# RTM_CON.net
KiCad netlist of a schematic drawn in Altium Designer
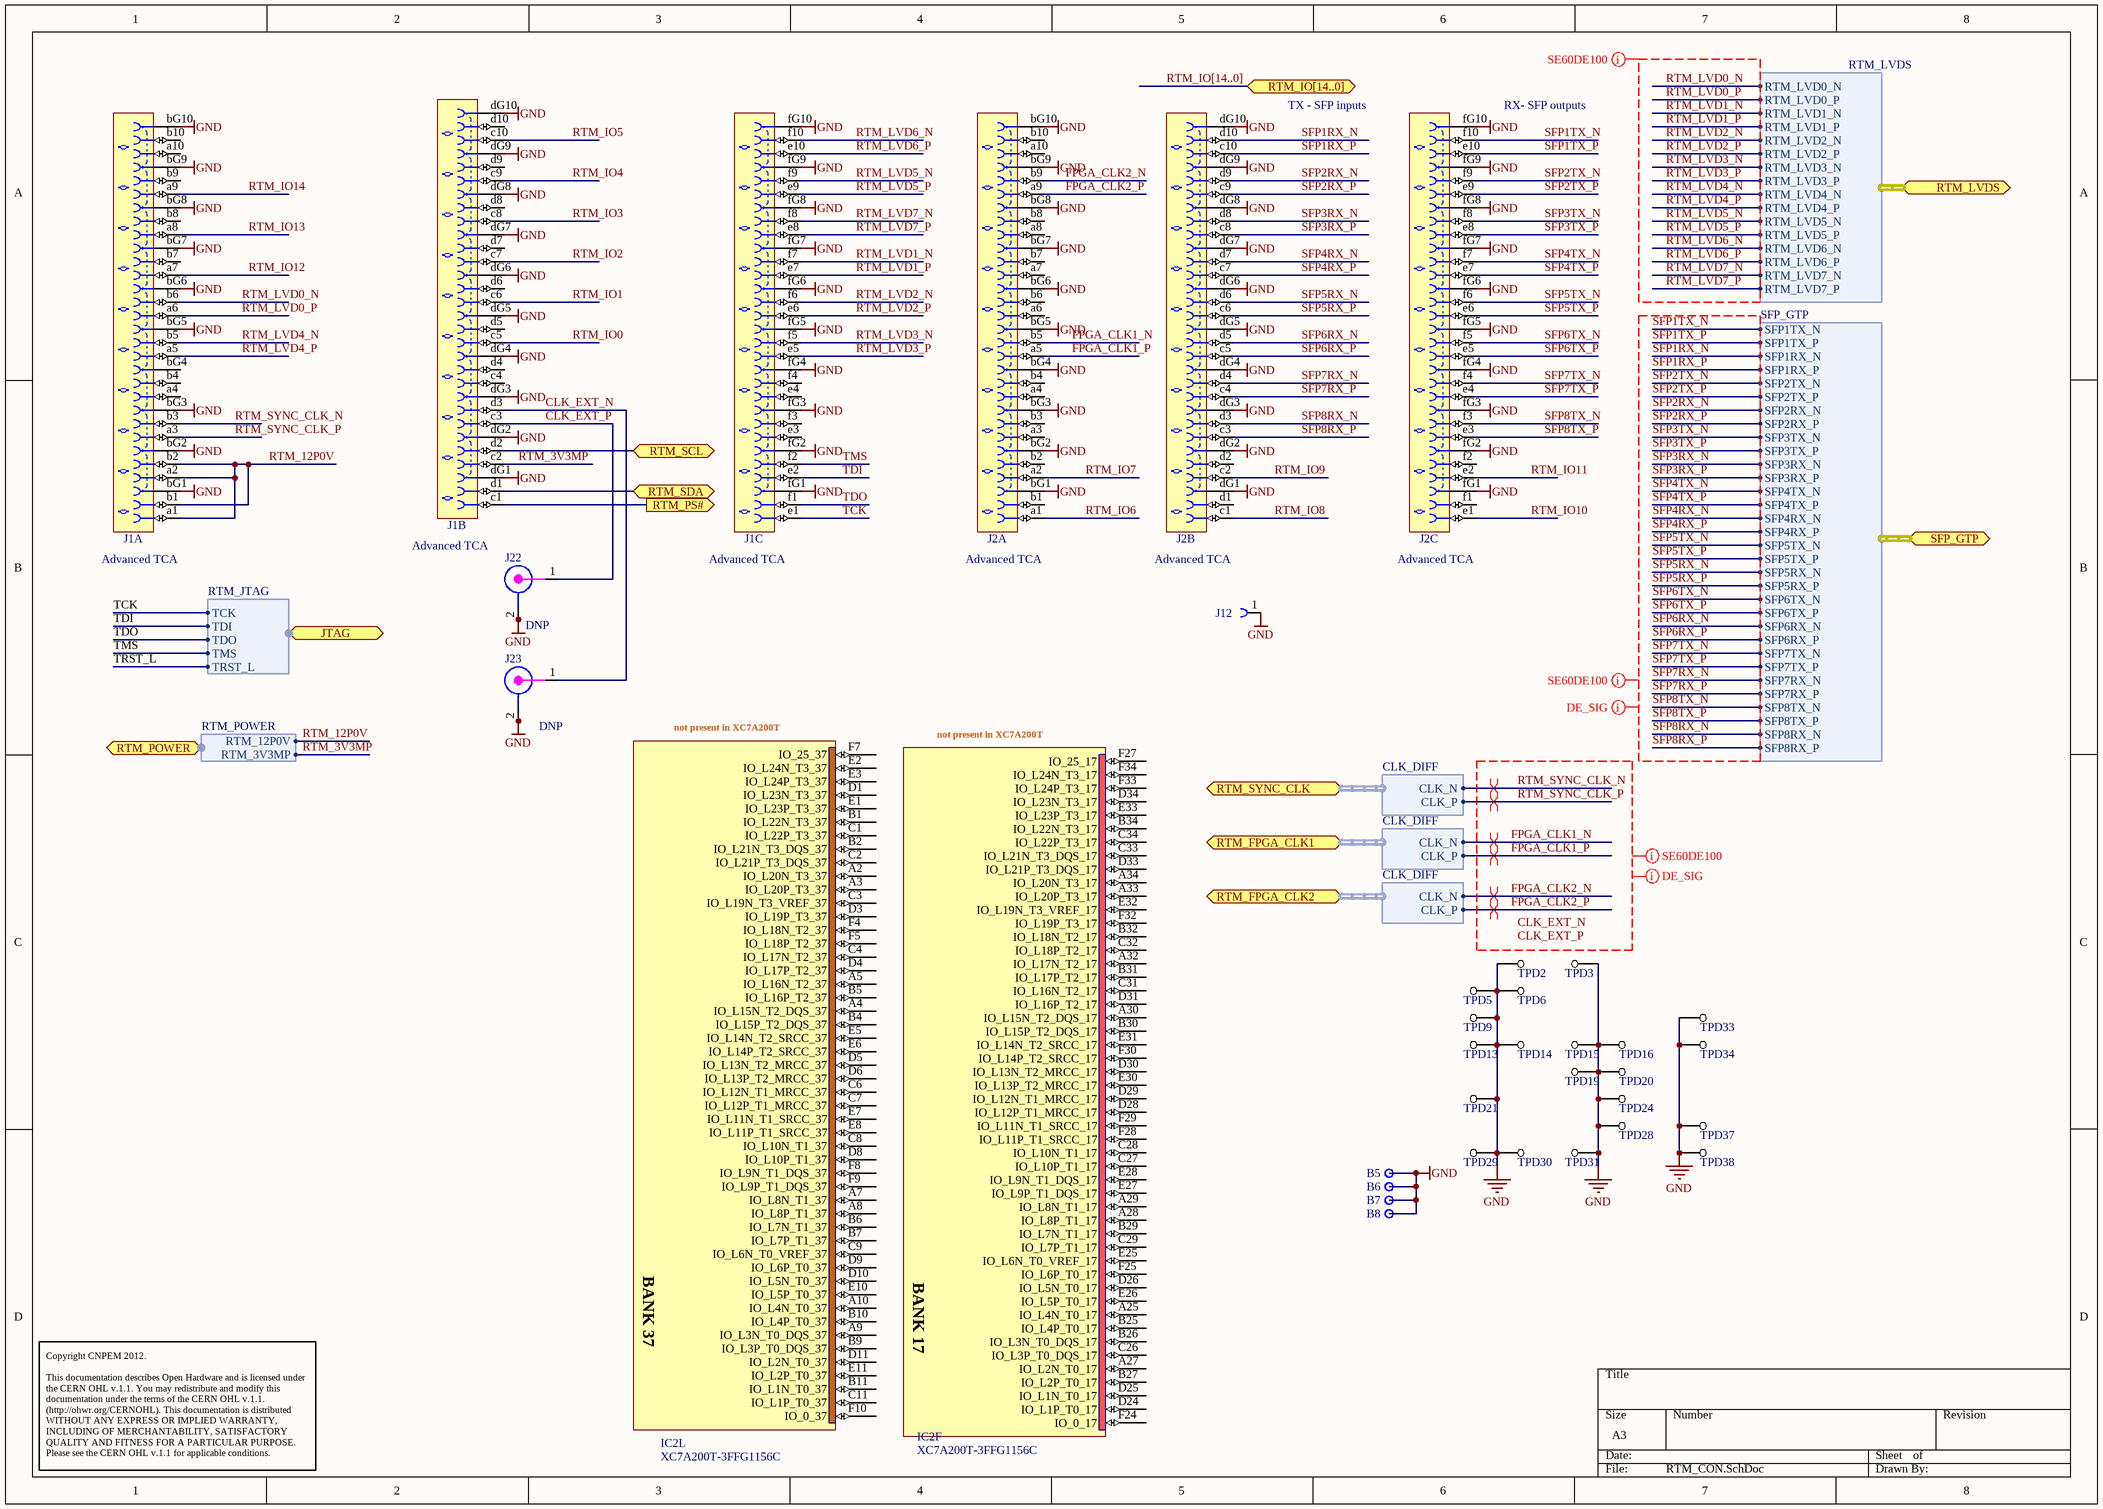
[diagram p0: RTM_CON.SchDoc]

(export (version "E")
  (design (tool "Eeschema 10.0.6"))
  (components
    (comp (ref "B5")
      (value "Test Point")
      (footprint "VERO_20-2136")
      (description "Single Terminal Socket")
      (fields
        (field (name "PART NUMBER") "VERO_20-2136")
        (field (name "MANUFACTURER") "VERO TECHNOLOGIES")
        (field (name "AUTHOR") "CERN DEM JLC")
      )
      (libsource (lib "Connectors") (part "Single Terminal Socket"))
    )
    (comp (ref "B6")
      (value "Test Point")
      (footprint "VERO_20-2136")
      (description "Single Terminal Socket")
      (fields
        (field (name "PART NUMBER") "VERO_20-2136")
        (field (name "MANUFACTURER") "VERO TECHNOLOGIES")
        (field (name "AUTHOR") "CERN DEM JLC")
      )
      (libsource (lib "Connectors") (part "Single Terminal Socket"))
    )
    (comp (ref "B7")
      (value "Test Point")
      (footprint "VERO_20-2136")
      (description "Single Terminal Socket")
      (fields
        (field (name "PART NUMBER") "VERO_20-2136")
        (field (name "MANUFACTURER") "VERO TECHNOLOGIES")
        (field (name "AUTHOR") "CERN DEM JLC")
      )
      (libsource (lib "Connectors") (part "Single Terminal Socket"))
    )
    (comp (ref "B8")
      (value "Test Point")
      (footprint "VERO_20-2136")
      (description "Single Terminal Socket")
      (fields
        (field (name "PART NUMBER") "VERO_20-2136")
        (field (name "MANUFACTURER") "VERO TECHNOLOGIES")
        (field (name "AUTHOR") "CERN DEM JLC")
      )
      (libsource (lib "Connectors") (part "Single Terminal Socket"))
    )
    (comp (ref "IC2")
      (value "XC7A200T-3FFG1156C")
      (footprint "BGA1156C100P34X34_3500X3500X335")
      (description "Artix-6 FPGA, 16 GTPs, 600 User I/Os, 1156-Pin BGA, Speed Grade 2, Commercial Grade, Pb-Free")
      (fields (field (name "MANUFACTURER") "XILINX") (field (name "AUTHOR") "CERN DEM JLC"))
      (libsource (lib "AMC_FMC_Carrier") (part "XC7A200T-3FFG1156C"))
    )
    (comp (ref "J1")
      (value "Advanced TCA")
      (footprint "TYCO_6469081-1")
      (description "Connector 60 ATCA Female 30 Pairs (60 Signals) + 3x10 Ground")
      (fields
        (field (name "PART NUMBER") "TYCO_6469081-1")
        (field (name "MANUFACTURER") "TYCO ELECTRONICS")
        (field (name "AUTHOR") "CERN DEM JLC")
      )
      (libsource (lib "Connectors") (part "Connector ATCA 60+30 Female"))
    )
    (comp (ref "J2")
      (value "Advanced TCA")
      (footprint "TYCO_6469081-1")
      (description "Connector 60 ATCA Female 30 Pairs (60 Signals) + 3x10 Ground")
      (fields
        (field (name "PART NUMBER") "TYCO_6469081-1")
        (field (name "MANUFACTURER") "TYCO ELECTRONICS")
        (field (name "AUTHOR") "CERN DEM JLC")
      )
      (libsource (lib "Connectors") (part "Connector ATCA 60+30 Female"))
    )
    (comp (ref "J12")
      (value "~")
      (footprint "TYCO_5120913-1")
      (description "Single Pin Female")
      (fields (field (name "PART NUMBER") "TYCO_5120913-1"))
      (libsource (lib "Connectors") (part "Single Pin Female"))
    )
    (comp (ref "J22")
      (value "DNP")
      (footprint "CON_UFL_HIROSE_RECEPTACLE")
      (description "UFL")
      (libsource (lib "LIBRARY_SCH") (part "CON_UFL_SMD"))
    )
    (comp (ref "J23")
      (value "DNP")
      (footprint "CON_UFL_HIROSE_RECEPTACLE")
      (description "UFL")
      (libsource (lib "LIBRARY_SCH") (part "CON_UFL_SMD"))
    )
    (comp (ref "TPD2")
      (value "Test Point")
      (footprint "TP_DIFF_0805")
      (description "1625854-2")
      (fields (field (name "PART NUMBER") "TP_DIFF"))
      (libsource (lib "Markers") (part "TP_SMD_DIFF"))
    )
    (comp (ref "TPD3")
      (value "Test Point")
      (footprint "TP_DIFF_0805")
      (description "1625854-2")
      (fields (field (name "PART NUMBER") "TP_DIFF"))
      (libsource (lib "Markers") (part "TP_SMD_DIFF"))
    )
    (comp (ref "TPD5")
      (value "Test Point")
      (footprint "TP_DIFF_0805")
      (description "1625854-2")
      (fields (field (name "PART NUMBER") "TP_DIFF"))
      (libsource (lib "Markers") (part "TP_SMD_DIFF"))
    )
    (comp (ref "TPD6")
      (value "Test Point")
      (footprint "TP_DIFF_0805")
      (description "1625854-2")
      (fields (field (name "PART NUMBER") "TP_DIFF"))
      (libsource (lib "Markers") (part "TP_SMD_DIFF"))
    )
    (comp (ref "TPD9")
      (value "Test Point")
      (footprint "TP_DIFF_0805")
      (description "1625854-2")
      (fields (field (name "PART NUMBER") "TP_DIFF"))
      (libsource (lib "Markers") (part "TP_SMD_DIFF"))
    )
    (comp (ref "TPD13")
      (value "Test Point")
      (footprint "TP_DIFF_0805")
      (description "1625854-2")
      (fields (field (name "PART NUMBER") "TP_DIFF"))
      (libsource (lib "Markers") (part "TP_SMD_DIFF"))
    )
    (comp (ref "TPD14")
      (value "Test Point")
      (footprint "TP_DIFF_0805")
      (description "1625854-2")
      (fields (field (name "PART NUMBER") "TP_DIFF"))
      (libsource (lib "Markers") (part "TP_SMD_DIFF"))
    )
    (comp (ref "TPD15")
      (value "Test Point")
      (footprint "TP_DIFF_0805")
      (description "1625854-2")
      (fields (field (name "PART NUMBER") "TP_DIFF"))
      (libsource (lib "Markers") (part "TP_SMD_DIFF"))
    )
    (comp (ref "TPD16")
      (value "Test Point")
      (footprint "TP_DIFF_0805")
      (description "1625854-2")
      (fields (field (name "PART NUMBER") "TP_DIFF"))
      (libsource (lib "Markers") (part "TP_SMD_DIFF"))
    )
    (comp (ref "TPD19")
      (value "Test Point")
      (footprint "TP_DIFF_0805")
      (description "1625854-2")
      (fields (field (name "PART NUMBER") "TP_DIFF"))
      (libsource (lib "Markers") (part "TP_SMD_DIFF"))
    )
    (comp (ref "TPD20")
      (value "Test Point")
      (footprint "TP_DIFF_0805")
      (description "1625854-2")
      (fields (field (name "PART NUMBER") "TP_DIFF"))
      (libsource (lib "Markers") (part "TP_SMD_DIFF"))
    )
    (comp (ref "TPD21")
      (value "Test Point")
      (footprint "TP_DIFF_0805")
      (description "1625854-2")
      (fields (field (name "PART NUMBER") "TP_DIFF"))
      (libsource (lib "Markers") (part "TP_SMD_DIFF"))
    )
    (comp (ref "TPD24")
      (value "Test Point")
      (footprint "TP_DIFF_0805")
      (description "1625854-2")
      (fields (field (name "PART NUMBER") "TP_DIFF"))
      (libsource (lib "Markers") (part "TP_SMD_DIFF"))
    )
    (comp (ref "TPD28")
      (value "Test Point")
      (footprint "TP_DIFF_0805")
      (description "1625854-2")
      (fields (field (name "PART NUMBER") "TP_DIFF"))
      (libsource (lib "Markers") (part "TP_SMD_DIFF"))
    )
    (comp (ref "TPD29")
      (value "Test Point")
      (footprint "TP_DIFF_0805")
      (description "1625854-2")
      (fields (field (name "PART NUMBER") "TP_DIFF"))
      (libsource (lib "Markers") (part "TP_SMD_DIFF"))
    )
    (comp (ref "TPD30")
      (value "Test Point")
      (footprint "TP_DIFF_0805")
      (description "1625854-2")
      (fields (field (name "PART NUMBER") "TP_DIFF"))
      (libsource (lib "Markers") (part "TP_SMD_DIFF"))
    )
    (comp (ref "TPD31")
      (value "Test Point")
      (footprint "TP_DIFF_0805")
      (description "1625854-2")
      (fields (field (name "PART NUMBER") "TP_DIFF"))
      (libsource (lib "Markers") (part "TP_SMD_DIFF"))
    )
    (comp (ref "TPD33")
      (value "Test Point")
      (footprint "TP_DIFF_0805")
      (description "1625854-2")
      (fields (field (name "PART NUMBER") "TP_DIFF"))
      (libsource (lib "Markers") (part "TP_SMD_DIFF"))
    )
    (comp (ref "TPD34")
      (value "Test Point")
      (footprint "TP_DIFF_0805")
      (description "1625854-2")
      (fields (field (name "PART NUMBER") "TP_DIFF"))
      (libsource (lib "Markers") (part "TP_SMD_DIFF"))
    )
    (comp (ref "TPD37")
      (value "Test Point")
      (footprint "TP_DIFF_0805")
      (description "1625854-2")
      (fields (field (name "PART NUMBER") "TP_DIFF"))
      (libsource (lib "Markers") (part "TP_SMD_DIFF"))
    )
    (comp (ref "TPD38")
      (value "Test Point")
      (footprint "TP_DIFF_0805")
      (description "1625854-2")
      (fields (field (name "PART NUMBER") "TP_DIFF"))
      (libsource (lib "Markers") (part "TP_SMD_DIFF"))
    )
  )
  (nets
    (net (code "6") (name "/CLK_EXT_N") (class "Default")
      (node (ref "J1") (pin "d3") (pinfunction "d3_d3") (pintype "bidirectional"))
      (node (ref "J23") (pin "1") (pintype "passive"))
    )
    (net (code "7") (name "/CLK_EXT_P") (class "Default")
      (node (ref "J1") (pin "c3") (pinfunction "c3_c3") (pintype "bidirectional"))
      (node (ref "J22") (pin "1") (pintype "passive"))
    )
    (net (code "8") (name "/FPGA_CLK1_N") (class "Default")
      (node (ref "J2") (pin "b5") (pinfunction "b5_b5") (pintype "bidirectional"))
    )
    (net (code "9") (name "/FPGA_CLK1_P") (class "Default")
      (node (ref "J2") (pin "a5") (pinfunction "a5_a5") (pintype "bidirectional"))
    )
    (net (code "10") (name "/FPGA_CLK2_N") (class "Default")
      (node (ref "J2") (pin "b9") (pinfunction "b9_b9") (pintype "bidirectional"))
    )
    (net (code "11") (name "/FPGA_CLK2_P") (class "Default")
      (node (ref "J2") (pin "a9") (pinfunction "a9_a9") (pintype "bidirectional"))
    )
    (net (code "12") (name "/RTM_3V3MP") (class "Default")
      (node (ref "J1") (pin "c2") (pinfunction "c2_c2") (pintype "bidirectional"))
    )
    (net (code "13") (name "/RTM_12P0V") (class "Default")
      (node (ref "J1") (pin "a1") (pinfunction "a1_a1") (pintype "bidirectional"))
      (node (ref "J1") (pin "a2") (pinfunction "a2_a2") (pintype "bidirectional"))
      (node (ref "J1") (pin "b1") (pinfunction "b1_b1") (pintype "bidirectional"))
      (node (ref "J1") (pin "b2") (pinfunction "b2_b2") (pintype "bidirectional"))
    )
    (net (code "14") (name "/RTM_IO0") (class "Default")
      (node (ref "J1") (pin "c5") (pinfunction "c5_c5") (pintype "bidirectional"))
    )
    (net (code "15") (name "/RTM_IO1") (class "Default")
      (node (ref "J1") (pin "c6") (pinfunction "c6_c6") (pintype "bidirectional"))
    )
    (net (code "16") (name "/RTM_IO2") (class "Default")
      (node (ref "J1") (pin "c7") (pinfunction "c7_c7") (pintype "bidirectional"))
    )
    (net (code "17") (name "/RTM_IO3") (class "Default")
      (node (ref "J1") (pin "c8") (pinfunction "c8_c8") (pintype "bidirectional"))
    )
    (net (code "18") (name "/RTM_IO4") (class "Default")
      (node (ref "J1") (pin "c9") (pinfunction "c9_c9") (pintype "bidirectional"))
    )
    (net (code "19") (name "/RTM_IO5") (class "Default")
      (node (ref "J1") (pin "c10") (pinfunction "c10_c10") (pintype "bidirectional"))
    )
    (net (code "20") (name "/RTM_IO6") (class "Default")
      (node (ref "J2") (pin "a1") (pinfunction "a1_a1") (pintype "bidirectional"))
    )
    (net (code "21") (name "/RTM_IO7") (class "Default")
      (node (ref "J2") (pin "a2") (pinfunction "a2_a2") (pintype "bidirectional"))
    )
    (net (code "22") (name "/RTM_IO8") (class "Default")
      (node (ref "J2") (pin "c1") (pinfunction "c1_c1") (pintype "bidirectional"))
    )
    (net (code "23") (name "/RTM_IO9") (class "Default")
      (node (ref "J2") (pin "c2") (pinfunction "c2_c2") (pintype "bidirectional"))
    )
    (net (code "24") (name "/RTM_IO10") (class "Default")
      (node (ref "J2") (pin "e1") (pinfunction "e1_e1") (pintype "bidirectional"))
    )
    (net (code "25") (name "/RTM_IO11") (class "Default")
      (node (ref "J2") (pin "e2") (pinfunction "e2_e2") (pintype "bidirectional"))
    )
    (net (code "26") (name "/RTM_IO12") (class "Default")
      (node (ref "J1") (pin "a7") (pinfunction "a7_a7") (pintype "bidirectional"))
    )
    (net (code "27") (name "/RTM_IO13") (class "Default")
      (node (ref "J1") (pin "a8") (pinfunction "a8_a8") (pintype "bidirectional"))
    )
    (net (code "28") (name "/RTM_IO14") (class "Default")
      (node (ref "J1") (pin "a9") (pinfunction "a9_a9") (pintype "bidirectional"))
    )
    (net (code "30") (name "/RTM_LVD0_N") (class "Default")
      (node (ref "J1") (pin "b6") (pinfunction "b6_b6") (pintype "bidirectional"))
    )
    (net (code "31") (name "/RTM_LVD0_P") (class "Default")
      (node (ref "J1") (pin "a6") (pinfunction "a6_a6") (pintype "bidirectional"))
    )
    (net (code "32") (name "/RTM_LVD1_N") (class "Default")
      (node (ref "J1") (pin "f7") (pinfunction "f7_f7") (pintype "bidirectional"))
    )
    (net (code "33") (name "/RTM_LVD1_P") (class "Default")
      (node (ref "J1") (pin "e7") (pinfunction "e7_e7") (pintype "bidirectional"))
    )
    (net (code "34") (name "/RTM_LVD2_N") (class "Default")
      (node (ref "J1") (pin "f6") (pinfunction "f6_f6") (pintype "bidirectional"))
    )
    (net (code "35") (name "/RTM_LVD2_P") (class "Default")
      (node (ref "J1") (pin "e6") (pinfunction "e6_e6") (pintype "bidirectional"))
    )
    (net (code "36") (name "/RTM_LVD3_N") (class "Default")
      (node (ref "J1") (pin "f5") (pinfunction "f5_f5") (pintype "bidirectional"))
    )
    (net (code "37") (name "/RTM_LVD3_P") (class "Default")
      (node (ref "J1") (pin "e5") (pinfunction "e5_e5") (pintype "bidirectional"))
    )
    (net (code "38") (name "/RTM_LVD4_N") (class "Default")
      (node (ref "J1") (pin "b5") (pinfunction "b5_b5") (pintype "bidirectional"))
    )
    (net (code "39") (name "/RTM_LVD4_P") (class "Default")
      (node (ref "J1") (pin "a5") (pinfunction "a5_a5") (pintype "bidirectional"))
    )
    (net (code "40") (name "/RTM_LVD5_N") (class "Default")
      (node (ref "J1") (pin "f9") (pinfunction "f9_f9") (pintype "bidirectional"))
    )
    (net (code "41") (name "/RTM_LVD5_P") (class "Default")
      (node (ref "J1") (pin "e9") (pinfunction "e9_e9") (pintype "bidirectional"))
    )
    (net (code "42") (name "/RTM_LVD6_N") (class "Default")
      (node (ref "J1") (pin "f10") (pinfunction "f10_f10") (pintype "bidirectional"))
    )
    (net (code "43") (name "/RTM_LVD6_P") (class "Default")
      (node (ref "J1") (pin "e10") (pinfunction "e10_e10") (pintype "bidirectional"))
    )
    (net (code "44") (name "/RTM_LVD7_N") (class "Default")
      (node (ref "J1") (pin "f8") (pinfunction "f8_f8") (pintype "bidirectional"))
    )
    (net (code "45") (name "/RTM_LVD7_P") (class "Default")
      (node (ref "J1") (pin "e8") (pinfunction "e8_e8") (pintype "bidirectional"))
    )
    (net (code "46") (name "/RTM_PS#") (class "Default")
      (node (ref "J1") (pin "c1") (pinfunction "c1_c1") (pintype "bidirectional"))
    )
    (net (code "47") (name "/RTM_SCL") (class "Default")
      (node (ref "J1") (pin "d2") (pinfunction "d2_d2") (pintype "bidirectional"))
    )
    (net (code "48") (name "/RTM_SDA") (class "Default")
      (node (ref "J1") (pin "d1") (pinfunction "d1_d1") (pintype "bidirectional"))
    )
    (net (code "49") (name "/RTM_SYNC_CLK_N") (class "Default")
      (node (ref "J1") (pin "b3") (pinfunction "b3_b3") (pintype "bidirectional"))
    )
    (net (code "50") (name "/RTM_SYNC_CLK_P") (class "Default")
      (node (ref "J1") (pin "a3") (pinfunction "a3_a3") (pintype "bidirectional"))
    )
    (net (code "51") (name "/SFP1RX_N") (class "Default")
      (node (ref "J2") (pin "d10") (pinfunction "d10_d10") (pintype "bidirectional"))
    )
    (net (code "52") (name "/SFP1RX_P") (class "Default")
      (node (ref "J2") (pin "c10") (pinfunction "c10_c10") (pintype "bidirectional"))
    )
    (net (code "53") (name "/SFP1TX_N") (class "Default")
      (node (ref "J2") (pin "f10") (pinfunction "f10_f10") (pintype "bidirectional"))
    )
    (net (code "54") (name "/SFP1TX_P") (class "Default")
      (node (ref "J2") (pin "e10") (pinfunction "e10_e10") (pintype "bidirectional"))
    )
    (net (code "55") (name "/SFP2RX_N") (class "Default")
      (node (ref "J2") (pin "d9") (pinfunction "d9_d9") (pintype "bidirectional"))
    )
    (net (code "56") (name "/SFP2RX_P") (class "Default")
      (node (ref "J2") (pin "c9") (pinfunction "c9_c9") (pintype "bidirectional"))
    )
    (net (code "57") (name "/SFP2TX_N") (class "Default")
      (node (ref "J2") (pin "f9") (pinfunction "f9_f9") (pintype "bidirectional"))
    )
    (net (code "58") (name "/SFP2TX_P") (class "Default")
      (node (ref "J2") (pin "e9") (pinfunction "e9_e9") (pintype "bidirectional"))
    )
    (net (code "59") (name "/SFP3RX_N") (class "Default")
      (node (ref "J2") (pin "d8") (pinfunction "d8_d8") (pintype "bidirectional"))
    )
    (net (code "60") (name "/SFP3RX_P") (class "Default")
      (node (ref "J2") (pin "c8") (pinfunction "c8_c8") (pintype "bidirectional"))
    )
    (net (code "61") (name "/SFP3TX_N") (class "Default")
      (node (ref "J2") (pin "f8") (pinfunction "f8_f8") (pintype "bidirectional"))
    )
    (net (code "62") (name "/SFP3TX_P") (class "Default")
      (node (ref "J2") (pin "e8") (pinfunction "e8_e8") (pintype "bidirectional"))
    )
    (net (code "63") (name "/SFP4RX_N") (class "Default")
      (node (ref "J2") (pin "d7") (pinfunction "d7_d7") (pintype "bidirectional"))
    )
    (net (code "64") (name "/SFP4RX_P") (class "Default")
      (node (ref "J2") (pin "c7") (pinfunction "c7_c7") (pintype "bidirectional"))
    )
    (net (code "65") (name "/SFP4TX_N") (class "Default")
      (node (ref "J2") (pin "f7") (pinfunction "f7_f7") (pintype "bidirectional"))
    )
    (net (code "66") (name "/SFP4TX_P") (class "Default")
      (node (ref "J2") (pin "e7") (pinfunction "e7_e7") (pintype "bidirectional"))
    )
    (net (code "67") (name "/SFP5RX_N") (class "Default")
      (node (ref "J2") (pin "d6") (pinfunction "d6_d6") (pintype "bidirectional"))
    )
    (net (code "68") (name "/SFP5RX_P") (class "Default")
      (node (ref "J2") (pin "c6") (pinfunction "c6_c6") (pintype "bidirectional"))
    )
    (net (code "69") (name "/SFP5TX_N") (class "Default")
      (node (ref "J2") (pin "f6") (pinfunction "f6_f6") (pintype "bidirectional"))
    )
    (net (code "70") (name "/SFP5TX_P") (class "Default")
      (node (ref "J2") (pin "e6") (pinfunction "e6_e6") (pintype "bidirectional"))
    )
    (net (code "71") (name "/SFP6RX_N") (class "Default")
      (node (ref "J2") (pin "d5") (pinfunction "d5_d5") (pintype "bidirectional"))
    )
    (net (code "72") (name "/SFP6RX_P") (class "Default")
      (node (ref "J2") (pin "c5") (pinfunction "c5_c5") (pintype "bidirectional"))
    )
    (net (code "73") (name "/SFP6TX_N") (class "Default")
      (node (ref "J2") (pin "f5") (pinfunction "f5_f5") (pintype "bidirectional"))
    )
    (net (code "74") (name "/SFP6TX_P") (class "Default")
      (node (ref "J2") (pin "e5") (pinfunction "e5_e5") (pintype "bidirectional"))
    )
    (net (code "75") (name "/SFP7RX_N") (class "Default")
      (node (ref "J2") (pin "d4") (pinfunction "d4_d4") (pintype "bidirectional"))
    )
    (net (code "76") (name "/SFP7RX_P") (class "Default")
      (node (ref "J2") (pin "c4") (pinfunction "c4_c4") (pintype "bidirectional"))
    )
    (net (code "77") (name "/SFP7TX_N") (class "Default")
      (node (ref "J2") (pin "f4") (pinfunction "f4_f4") (pintype "bidirectional"))
    )
    (net (code "78") (name "/SFP7TX_P") (class "Default")
      (node (ref "J2") (pin "e4") (pinfunction "e4_e4") (pintype "bidirectional"))
    )
    (net (code "79") (name "/SFP8RX_N") (class "Default")
      (node (ref "J2") (pin "d3") (pinfunction "d3_d3") (pintype "bidirectional"))
    )
    (net (code "80") (name "/SFP8RX_P") (class "Default")
      (node (ref "J2") (pin "c3") (pinfunction "c3_c3") (pintype "bidirectional"))
    )
    (net (code "81") (name "/SFP8TX_N") (class "Default")
      (node (ref "J2") (pin "f3") (pinfunction "f3_f3") (pintype "bidirectional"))
    )
    (net (code "82") (name "/SFP8TX_P") (class "Default")
      (node (ref "J2") (pin "e3") (pinfunction "e3_e3") (pintype "bidirectional"))
    )
    (net (code "83") (name "/TCK") (class "Default")
      (node (ref "J1") (pin "e1") (pinfunction "e1_e1") (pintype "bidirectional"))
    )
    (net (code "84") (name "/TDI") (class "Default")
      (node (ref "J1") (pin "e2") (pinfunction "e2_e2") (pintype "bidirectional"))
    )
    (net (code "85") (name "/TDO") (class "Default")
      (node (ref "J1") (pin "f1") (pinfunction "f1_f1") (pintype "bidirectional"))
    )
    (net (code "86") (name "/TMS") (class "Default")
      (node (ref "J1") (pin "f2") (pinfunction "f2_f2") (pintype "bidirectional"))
    )
    (net (code "93") (name "GND") (class "Default")
      (node (ref "B5") (pin "1") (pinfunction "1_1") (pintype "bidirectional"))
      (node (ref "B6") (pin "1") (pinfunction "1_1") (pintype "bidirectional"))
      (node (ref "B7") (pin "1") (pinfunction "1_1") (pintype "bidirectional"))
      (node (ref "B8") (pin "1") (pinfunction "1_1") (pintype "bidirectional"))
      (node (ref "J1") (pin "bG1") (pinfunction "bG1_bG1") (pintype "power_in"))
      (node (ref "J1") (pin "bG10") (pinfunction "bG10_bG10") (pintype "power_in"))
      (node (ref "J1") (pin "bG2") (pinfunction "bG2_bG2") (pintype "power_in"))
      (node (ref "J1") (pin "bG3") (pinfunction "bG3_bG3") (pintype "power_in"))
      (node (ref "J1") (pin "bG5") (pinfunction "bG5_bG5") (pintype "power_in"))
      (node (ref "J1") (pin "bG6") (pinfunction "bG6_bG6") (pintype "power_in"))
      (node (ref "J1") (pin "bG7") (pinfunction "bG7_bG7") (pintype "power_in"))
      (node (ref "J1") (pin "bG8") (pinfunction "bG8_bG8") (pintype "power_in"))
      (node (ref "J1") (pin "bG9") (pinfunction "bG9_bG9") (pintype "power_in"))
      (node (ref "J1") (pin "dG1") (pinfunction "dG1_dG1") (pintype "power_in"))
      (node (ref "J1") (pin "dG10") (pinfunction "dG10_dG10") (pintype "power_in"))
      (node (ref "J1") (pin "dG2") (pinfunction "dG2_dG2") (pintype "power_in"))
      (node (ref "J1") (pin "dG3") (pinfunction "dG3_dG3") (pintype "power_in"))
      (node (ref "J1") (pin "dG4") (pinfunction "dG4_dG4") (pintype "power_in"))
      (node (ref "J1") (pin "dG5") (pinfunction "dG5_dG5") (pintype "power_in"))
      (node (ref "J1") (pin "dG6") (pinfunction "dG6_dG6") (pintype "power_in"))
      (node (ref "J1") (pin "dG7") (pinfunction "dG7_dG7") (pintype "power_in"))
      (node (ref "J1") (pin "dG8") (pinfunction "dG8_dG8") (pintype "power_in"))
      (node (ref "J1") (pin "dG9") (pinfunction "dG9_dG9") (pintype "power_in"))
      (node (ref "J1") (pin "fG1") (pinfunction "fG1_fG1") (pintype "power_in"))
      (node (ref "J1") (pin "fG10") (pinfunction "fG10_fG10") (pintype "power_in"))
      (node (ref "J1") (pin "fG2") (pinfunction "fG2_fG2") (pintype "power_in"))
      (node (ref "J1") (pin "fG3") (pinfunction "fG3_fG3") (pintype "power_in"))
      (node (ref "J1") (pin "fG4") (pinfunction "fG4_fG4") (pintype "power_in"))
      (node (ref "J1") (pin "fG5") (pinfunction "fG5_fG5") (pintype "power_in"))
      (node (ref "J1") (pin "fG6") (pinfunction "fG6_fG6") (pintype "power_in"))
      (node (ref "J1") (pin "fG7") (pinfunction "fG7_fG7") (pintype "power_in"))
      (node (ref "J1") (pin "fG8") (pinfunction "fG8_fG8") (pintype "power_in"))
      (node (ref "J1") (pin "fG9") (pinfunction "fG9_fG9") (pintype "power_in"))
      (node (ref "J12") (pin "1") (pinfunction "1_1") (pintype "bidirectional"))
      (node (ref "J2") (pin "bG1") (pinfunction "bG1_bG1") (pintype "power_in"))
      (node (ref "J2") (pin "bG10") (pinfunction "bG10_bG10") (pintype "power_in"))
      (node (ref "J2") (pin "bG2") (pinfunction "bG2_bG2") (pintype "power_in"))
      (node (ref "J2") (pin "bG3") (pinfunction "bG3_bG3") (pintype "power_in"))
      (node (ref "J2") (pin "bG4") (pinfunction "bG4_bG4") (pintype "power_in"))
      (node (ref "J2") (pin "bG5") (pinfunction "bG5_bG5") (pintype "power_in"))
      (node (ref "J2") (pin "bG6") (pinfunction "bG6_bG6") (pintype "power_in"))
      (node (ref "J2") (pin "bG7") (pinfunction "bG7_bG7") (pintype "power_in"))
      (node (ref "J2") (pin "bG8") (pinfunction "bG8_bG8") (pintype "power_in"))
      (node (ref "J2") (pin "bG9") (pinfunction "bG9_bG9") (pintype "power_in"))
      (node (ref "J2") (pin "dG1") (pinfunction "dG1_dG1") (pintype "power_in"))
      (node (ref "J2") (pin "dG10") (pinfunction "dG10_dG10") (pintype "power_in"))
      (node (ref "J2") (pin "dG2") (pinfunction "dG2_dG2") (pintype "power_in"))
      (node (ref "J2") (pin "dG3") (pinfunction "dG3_dG3") (pintype "power_in"))
      (node (ref "J2") (pin "dG4") (pinfunction "dG4_dG4") (pintype "power_in"))
      (node (ref "J2") (pin "dG5") (pinfunction "dG5_dG5") (pintype "power_in"))
      (node (ref "J2") (pin "dG6") (pinfunction "dG6_dG6") (pintype "power_in"))
      (node (ref "J2") (pin "dG7") (pinfunction "dG7_dG7") (pintype "power_in"))
      (node (ref "J2") (pin "dG8") (pinfunction "dG8_dG8") (pintype "power_in"))
      (node (ref "J2") (pin "dG9") (pinfunction "dG9_dG9") (pintype "power_in"))
      (node (ref "J2") (pin "fG1") (pinfunction "fG1_fG1") (pintype "power_in"))
      (node (ref "J2") (pin "fG10") (pinfunction "fG10_fG10") (pintype "power_in"))
      (node (ref "J2") (pin "fG2") (pinfunction "fG2_fG2") (pintype "power_in"))
      (node (ref "J2") (pin "fG3") (pinfunction "fG3_fG3") (pintype "power_in"))
      (node (ref "J2") (pin "fG4") (pinfunction "fG4_fG4") (pintype "power_in"))
      (node (ref "J2") (pin "fG5") (pinfunction "fG5_fG5") (pintype "power_in"))
      (node (ref "J2") (pin "fG6") (pinfunction "fG6_fG6") (pintype "power_in"))
      (node (ref "J2") (pin "fG7") (pinfunction "fG7_fG7") (pintype "power_in"))
      (node (ref "J2") (pin "fG8") (pinfunction "fG8_fG8") (pintype "power_in"))
      (node (ref "J2") (pin "fG9") (pinfunction "fG9_fG9") (pintype "power_in"))
      (node (ref "J22") (pin "2") (pintype "passive"))
      (node (ref "J22") (pin "2a") (pinfunction "GND_2a") (pintype "passive"))
      (node (ref "J23") (pin "2") (pintype "passive"))
      (node (ref "J23") (pin "2a") (pinfunction "GND_2a") (pintype "passive"))
      (node (ref "TPD13") (pin "1") (pinfunction "TP_1") (pintype "passive"))
      (node (ref "TPD14") (pin "1") (pinfunction "TP_1") (pintype "passive"))
      (node (ref "TPD15") (pin "1") (pinfunction "TP_1") (pintype "passive"))
      (node (ref "TPD16") (pin "1") (pinfunction "TP_1") (pintype "passive"))
      (node (ref "TPD19") (pin "1") (pinfunction "TP_1") (pintype "passive"))
      (node (ref "TPD2") (pin "1") (pinfunction "TP_1") (pintype "passive"))
      (node (ref "TPD20") (pin "1") (pinfunction "TP_1") (pintype "passive"))
      (node (ref "TPD21") (pin "1") (pinfunction "TP_1") (pintype "passive"))
      (node (ref "TPD24") (pin "1") (pinfunction "TP_1") (pintype "passive"))
      (node (ref "TPD28") (pin "1") (pinfunction "TP_1") (pintype "passive"))
      (node (ref "TPD29") (pin "1") (pinfunction "TP_1") (pintype "passive"))
      (node (ref "TPD3") (pin "1") (pinfunction "TP_1") (pintype "passive"))
      (node (ref "TPD30") (pin "1") (pinfunction "TP_1") (pintype "passive"))
      (node (ref "TPD31") (pin "1") (pinfunction "TP_1") (pintype "passive"))
      (node (ref "TPD33") (pin "1") (pinfunction "TP_1") (pintype "passive"))
      (node (ref "TPD34") (pin "1") (pinfunction "TP_1") (pintype "passive"))
      (node (ref "TPD37") (pin "1") (pinfunction "TP_1") (pintype "passive"))
      (node (ref "TPD38") (pin "1") (pinfunction "TP_1") (pintype "passive"))
      (node (ref "TPD5") (pin "1") (pinfunction "TP_1") (pintype "passive"))
      (node (ref "TPD6") (pin "1") (pinfunction "TP_1") (pintype "passive"))
      (node (ref "TPD9") (pin "1") (pinfunction "TP_1") (pintype "passive"))
    )
    (net (code "94") (name "unconnected-(IC2F-IO_0_17-PadF24)") (class "Default")
      (node (ref "IC2") (pin "F24") (pinfunction "IO_0_17_F24") (pintype "bidirectional"))
    )
    (net (code "95") (name "unconnected-(IC2F-IO_25_17-PadF27)") (class "Default")
      (node (ref "IC2") (pin "F27") (pinfunction "IO_25_17_F27") (pintype "bidirectional"))
    )
    (net (code "96") (name "unconnected-(IC2F-IO_L1N_T0_17-PadD25)") (class "Default")
      (node (ref "IC2") (pin "D25") (pinfunction "IO_L1N_T0_17_D25") (pintype "bidirectional"))
    )
    (net (code "97") (name "unconnected-(IC2F-IO_L1P_T0_17-PadD24)") (class "Default")
      (node (ref "IC2") (pin "D24") (pinfunction "IO_L1P_T0_17_D24") (pintype "bidirectional"))
    )
    (net (code "98") (name "unconnected-(IC2F-IO_L2N_T0_17-PadA27)") (class "Default")
      (node (ref "IC2") (pin "A27") (pinfunction "IO_L2N_T0_17_A27") (pintype "bidirectional"))
    )
    (net (code "99") (name "unconnected-(IC2F-IO_L2P_T0_17-PadB27)") (class "Default")
      (node (ref "IC2") (pin "B27") (pinfunction "IO_L2P_T0_17_B27") (pintype "bidirectional"))
    )
    (net (code "100") (name "unconnected-(IC2F-IO_L3N_T0_DQS_17-PadB26)") (class "Default")
      (node (ref "IC2") (pin "B26") (pinfunction "IO_L3N_T0_DQS_17_B26") (pintype "bidirectional"))
    )
    (net (code "101") (name "unconnected-(IC2F-IO_L3P_T0_DQS_17-PadC26)") (class "Default")
      (node (ref "IC2") (pin "C26") (pinfunction "IO_L3P_T0_DQS_17_C26") (pintype "bidirectional"))
    )
    (net (code "102") (name "unconnected-(IC2F-IO_L4N_T0_17-PadA25)") (class "Default")
      (node (ref "IC2") (pin "A25") (pinfunction "IO_L4N_T0_17_A25") (pintype "bidirectional"))
    )
    (net (code "103") (name "unconnected-(IC2F-IO_L4P_T0_17-PadB25)") (class "Default")
      (node (ref "IC2") (pin "B25") (pinfunction "IO_L4P_T0_17_B25") (pintype "bidirectional"))
    )
    (net (code "104") (name "unconnected-(IC2F-IO_L5N_T0_17-PadD26)") (class "Default")
      (node (ref "IC2") (pin "D26") (pinfunction "IO_L5N_T0_17_D26") (pintype "bidirectional"))
    )
    (net (code "105") (name "unconnected-(IC2F-IO_L5P_T0_17-PadE26)") (class "Default")
      (node (ref "IC2") (pin "E26") (pinfunction "IO_L5P_T0_17_E26") (pintype "bidirectional"))
    )
    (net (code "106") (name "unconnected-(IC2F-IO_L6N_T0_VREF_17-PadE25)") (class "Default")
      (node (ref "IC2") (pin "E25") (pinfunction "IO_L6N_T0_VREF_17_E25") (pintype "bidirectional"))
    )
    (net (code "107") (name "unconnected-(IC2F-IO_L6P_T0_17-PadF25)") (class "Default")
      (node (ref "IC2") (pin "F25") (pinfunction "IO_L6P_T0_17_F25") (pintype "bidirectional"))
    )
    (net (code "108") (name "unconnected-(IC2F-IO_L7N_T1_17-PadB29)") (class "Default")
      (node (ref "IC2") (pin "B29") (pinfunction "IO_L7N_T1_17_B29") (pintype "bidirectional"))
    )
    (net (code "109") (name "unconnected-(IC2F-IO_L7P_T1_17-PadC29)") (class "Default")
      (node (ref "IC2") (pin "C29") (pinfunction "IO_L7P_T1_17_C29") (pintype "bidirectional"))
    )
    (net (code "110") (name "unconnected-(IC2F-IO_L8N_T1_17-PadA29)") (class "Default")
      (node (ref "IC2") (pin "A29") (pinfunction "IO_L8N_T1_17_A29") (pintype "bidirectional"))
    )
    (net (code "111") (name "unconnected-(IC2F-IO_L8P_T1_17-PadA28)") (class "Default")
      (node (ref "IC2") (pin "A28") (pinfunction "IO_L8P_T1_17_A28") (pintype "bidirectional"))
    )
    (net (code "112") (name "unconnected-(IC2F-IO_L9N_T1_DQS_17-PadE28)") (class "Default")
      (node (ref "IC2") (pin "E28") (pinfunction "IO_L9N_T1_DQS_17_E28") (pintype "bidirectional"))
    )
    (net (code "113") (name "unconnected-(IC2F-IO_L9P_T1_DQS_17-PadE27)") (class "Default")
      (node (ref "IC2") (pin "E27") (pinfunction "IO_L9P_T1_DQS_17_E27") (pintype "bidirectional"))
    )
    (net (code "114") (name "unconnected-(IC2F-IO_L10N_T1_17-PadC28)") (class "Default")
      (node (ref "IC2") (pin "C28") (pinfunction "IO_L10N_T1_17_C28") (pintype "bidirectional"))
    )
    (net (code "115") (name "unconnected-(IC2F-IO_L10P_T1_17-PadC27)") (class "Default")
      (node (ref "IC2") (pin "C27") (pinfunction "IO_L10P_T1_17_C27") (pintype "bidirectional"))
    )
    (net (code "116") (name "unconnected-(IC2F-IO_L11N_T1_SRCC_17-PadF29)") (class "Default")
      (node (ref "IC2") (pin "F29") (pinfunction "IO_L11N_T1_SRCC_17_F29") (pintype "bidirectional"))
    )
    (net (code "117") (name "unconnected-(IC2F-IO_L11P_T1_SRCC_17-PadF28)") (class "Default")
      (node (ref "IC2") (pin "F28") (pinfunction "IO_L11P_T1_SRCC_17_F28") (pintype "bidirectional"))
    )
    (net (code "118") (name "unconnected-(IC2F-IO_L12N_T1_MRCC_17-PadD29)") (class "Default")
      (node (ref "IC2") (pin "D29") (pinfunction "IO_L12N_T1_MRCC_17_D29") (pintype "bidirectional"))
    )
    (net (code "119") (name "unconnected-(IC2F-IO_L12P_T1_MRCC_17-PadD28)") (class "Default")
      (node (ref "IC2") (pin "D28") (pinfunction "IO_L12P_T1_MRCC_17_D28") (pintype "bidirectional"))
    )
    (net (code "120") (name "unconnected-(IC2F-IO_L13N_T2_MRCC_17-PadD30)") (class "Default")
      (node (ref "IC2") (pin "D30") (pinfunction "IO_L13N_T2_MRCC_17_D30") (pintype "bidirectional"))
    )
    (net (code "121") (name "unconnected-(IC2F-IO_L13P_T2_MRCC_17-PadE30)") (class "Default")
      (node (ref "IC2") (pin "E30") (pinfunction "IO_L13P_T2_MRCC_17_E30") (pintype "bidirectional"))
    )
    (net (code "122") (name "unconnected-(IC2F-IO_L14N_T2_SRCC_17-PadE31)") (class "Default")
      (node (ref "IC2") (pin "E31") (pinfunction "IO_L14N_T2_SRCC_17_E31") (pintype "bidirectional"))
    )
    (net (code "123") (name "unconnected-(IC2F-IO_L14P_T2_SRCC_17-PadF30)") (class "Default")
      (node (ref "IC2") (pin "F30") (pinfunction "IO_L14P_T2_SRCC_17_F30") (pintype "bidirectional"))
    )
    (net (code "124") (name "unconnected-(IC2F-IO_L15N_T2_DQS_17-PadA30)") (class "Default")
      (node (ref "IC2") (pin "A30") (pinfunction "IO_L15N_T2_DQS_17_A30") (pintype "bidirectional"))
    )
    (net (code "125") (name "unconnected-(IC2F-IO_L15P_T2_DQS_17-PadB30)") (class "Default")
      (node (ref "IC2") (pin "B30") (pinfunction "IO_L15P_T2_DQS_17_B30") (pintype "bidirectional"))
    )
    (net (code "126") (name "unconnected-(IC2F-IO_L16N_T2_17-PadC31)") (class "Default")
      (node (ref "IC2") (pin "C31") (pinfunction "IO_L16N_T2_17_C31") (pintype "bidirectional"))
    )
    (net (code "127") (name "unconnected-(IC2F-IO_L16P_T2_17-PadD31)") (class "Default")
      (node (ref "IC2") (pin "D31") (pinfunction "IO_L16P_T2_17_D31") (pintype "bidirectional"))
    )
    (net (code "128") (name "unconnected-(IC2F-IO_L17N_T2_17-PadA32)") (class "Default")
      (node (ref "IC2") (pin "A32") (pinfunction "IO_L17N_T2_17_A32") (pintype "bidirectional"))
    )
    (net (code "129") (name "unconnected-(IC2F-IO_L17P_T2_17-PadB31)") (class "Default")
      (node (ref "IC2") (pin "B31") (pinfunction "IO_L17P_T2_17_B31") (pintype "bidirectional"))
    )
    (net (code "130") (name "unconnected-(IC2F-IO_L18N_T2_17-PadB32)") (class "Default")
      (node (ref "IC2") (pin "B32") (pinfunction "IO_L18N_T2_17_B32") (pintype "bidirectional"))
    )
    (net (code "131") (name "unconnected-(IC2F-IO_L18P_T2_17-PadC32)") (class "Default")
      (node (ref "IC2") (pin "C32") (pinfunction "IO_L18P_T2_17_C32") (pintype "bidirectional"))
    )
    (net (code "132") (name "unconnected-(IC2F-IO_L19N_T3_VREF_17-PadE32)") (class "Default")
      (node (ref "IC2") (pin "E32") (pinfunction "IO_L19N_T3_VREF_17_E32") (pintype "bidirectional"))
    )
    (net (code "133") (name "unconnected-(IC2F-IO_L19P_T3_17-PadF32)") (class "Default")
      (node (ref "IC2") (pin "F32") (pinfunction "IO_L19P_T3_17_F32") (pintype "bidirectional"))
    )
    (net (code "134") (name "unconnected-(IC2F-IO_L20N_T3_17-PadA34)") (class "Default")
      (node (ref "IC2") (pin "A34") (pinfunction "IO_L20N_T3_17_A34") (pintype "bidirectional"))
    )
    (net (code "135") (name "unconnected-(IC2F-IO_L20P_T3_17-PadA33)") (class "Default")
      (node (ref "IC2") (pin "A33") (pinfunction "IO_L20P_T3_17_A33") (pintype "bidirectional"))
    )
    (net (code "136") (name "unconnected-(IC2F-IO_L21N_T3_DQS_17-PadC33)") (class "Default")
      (node (ref "IC2") (pin "C33") (pinfunction "IO_L21N_T3_DQS_17_C33") (pintype "bidirectional"))
    )
    (net (code "137") (name "unconnected-(IC2F-IO_L21P_T3_DQS_17-PadD33)") (class "Default")
      (node (ref "IC2") (pin "D33") (pinfunction "IO_L21P_T3_DQS_17_D33") (pintype "bidirectional"))
    )
    (net (code "138") (name "unconnected-(IC2F-IO_L22N_T3_17-PadB34)") (class "Default")
      (node (ref "IC2") (pin "B34") (pinfunction "IO_L22N_T3_17_B34") (pintype "bidirectional"))
    )
    (net (code "139") (name "unconnected-(IC2F-IO_L22P_T3_17-PadC34)") (class "Default")
      (node (ref "IC2") (pin "C34") (pinfunction "IO_L22P_T3_17_C34") (pintype "bidirectional"))
    )
    (net (code "140") (name "unconnected-(IC2F-IO_L23N_T3_17-PadD34)") (class "Default")
      (node (ref "IC2") (pin "D34") (pinfunction "IO_L23N_T3_17_D34") (pintype "bidirectional"))
    )
    (net (code "141") (name "unconnected-(IC2F-IO_L23P_T3_17-PadE33)") (class "Default")
      (node (ref "IC2") (pin "E33") (pinfunction "IO_L23P_T3_17_E33") (pintype "bidirectional"))
    )
    (net (code "142") (name "unconnected-(IC2F-IO_L24N_T3_17-PadF34)") (class "Default")
      (node (ref "IC2") (pin "F34") (pinfunction "IO_L24N_T3_17_F34") (pintype "bidirectional"))
    )
    (net (code "143") (name "unconnected-(IC2F-IO_L24P_T3_17-PadF33)") (class "Default")
      (node (ref "IC2") (pin "F33") (pinfunction "IO_L24P_T3_17_F33") (pintype "bidirectional"))
    )
    (net (code "144") (name "unconnected-(IC2L-IO_0_37-PadF10)") (class "Default")
      (node (ref "IC2") (pin "F10") (pinfunction "IO_0_37_F10") (pintype "bidirectional"))
    )
    (net (code "145") (name "unconnected-(IC2L-IO_25_37-PadF7)") (class "Default")
      (node (ref "IC2") (pin "F7") (pinfunction "IO_25_37_F7") (pintype "bidirectional"))
    )
    (net (code "146") (name "unconnected-(IC2L-IO_L1N_T0_37-PadB11)") (class "Default")
      (node (ref "IC2") (pin "B11") (pinfunction "IO_L1N_T0_37_B11") (pintype "bidirectional"))
    )
    (net (code "147") (name "unconnected-(IC2L-IO_L1P_T0_37-PadC11)") (class "Default")
      (node (ref "IC2") (pin "C11") (pinfunction "IO_L1P_T0_37_C11") (pintype "bidirectional"))
    )
    (net (code "148") (name "unconnected-(IC2L-IO_L2N_T0_37-PadD11)") (class "Default")
      (node (ref "IC2") (pin "D11") (pinfunction "IO_L2N_T0_37_D11") (pintype "bidirectional"))
    )
    (net (code "149") (name "unconnected-(IC2L-IO_L2P_T0_37-PadE11)") (class "Default")
      (node (ref "IC2") (pin "E11") (pinfunction "IO_L2P_T0_37_E11") (pintype "bidirectional"))
    )
    (net (code "150") (name "unconnected-(IC2L-IO_L3N_T0_DQS_37-PadA9)") (class "Default")
      (node (ref "IC2") (pin "A9") (pinfunction "IO_L3N_T0_DQS_37_A9") (pintype "bidirectional"))
    )
    (net (code "151") (name "unconnected-(IC2L-IO_L3P_T0_DQS_37-PadB9)") (class "Default")
      (node (ref "IC2") (pin "B9") (pinfunction "IO_L3P_T0_DQS_37_B9") (pintype "bidirectional"))
    )
    (net (code "152") (name "unconnected-(IC2L-IO_L4N_T0_37-PadA10)") (class "Default")
      (node (ref "IC2") (pin "A10") (pinfunction "IO_L4N_T0_37_A10") (pintype "bidirectional"))
    )
    (net (code "153") (name "unconnected-(IC2L-IO_L4P_T0_37-PadB10)") (class "Default")
      (node (ref "IC2") (pin "B10") (pinfunction "IO_L4P_T0_37_B10") (pintype "bidirectional"))
    )
    (net (code "154") (name "unconnected-(IC2L-IO_L5N_T0_37-PadD10)") (class "Default")
      (node (ref "IC2") (pin "D10") (pinfunction "IO_L5N_T0_37_D10") (pintype "bidirectional"))
    )
    (net (code "155") (name "unconnected-(IC2L-IO_L5P_T0_37-PadE10)") (class "Default")
      (node (ref "IC2") (pin "E10") (pinfunction "IO_L5P_T0_37_E10") (pintype "bidirectional"))
    )
    (net (code "156") (name "unconnected-(IC2L-IO_L6N_T0_VREF_37-PadC9)") (class "Default")
      (node (ref "IC2") (pin "C9") (pinfunction "IO_L6N_T0_VREF_37_C9") (pintype "bidirectional"))
    )
    (net (code "157") (name "unconnected-(IC2L-IO_L6P_T0_37-PadD9)") (class "Default")
      (node (ref "IC2") (pin "D9") (pinfunction "IO_L6P_T0_37_D9") (pintype "bidirectional"))
    )
    (net (code "158") (name "unconnected-(IC2L-IO_L7N_T1_37-PadB6)") (class "Default")
      (node (ref "IC2") (pin "B6") (pinfunction "IO_L7N_T1_37_B6") (pintype "bidirectional"))
    )
    (net (code "159") (name "unconnected-(IC2L-IO_L7P_T1_37-PadB7)") (class "Default")
      (node (ref "IC2") (pin "B7") (pinfunction "IO_L7P_T1_37_B7") (pintype "bidirectional"))
    )
    (net (code "160") (name "unconnected-(IC2L-IO_L8N_T1_37-PadA7)") (class "Default")
      (node (ref "IC2") (pin "A7") (pinfunction "IO_L8N_T1_37_A7") (pintype "bidirectional"))
    )
    (net (code "161") (name "unconnected-(IC2L-IO_L8P_T1_37-PadA8)") (class "Default")
      (node (ref "IC2") (pin "A8") (pinfunction "IO_L8P_T1_37_A8") (pintype "bidirectional"))
    )
    (net (code "162") (name "unconnected-(IC2L-IO_L9N_T1_DQS_37-PadF8)") (class "Default")
      (node (ref "IC2") (pin "F8") (pinfunction "IO_L9N_T1_DQS_37_F8") (pintype "bidirectional"))
    )
    (net (code "163") (name "unconnected-(IC2L-IO_L9P_T1_DQS_37-PadF9)") (class "Default")
      (node (ref "IC2") (pin "F9") (pinfunction "IO_L9P_T1_DQS_37_F9") (pintype "bidirectional"))
    )
    (net (code "164") (name "unconnected-(IC2L-IO_L10N_T1_37-PadC8)") (class "Default")
      (node (ref "IC2") (pin "C8") (pinfunction "IO_L10N_T1_37_C8") (pintype "bidirectional"))
    )
    (net (code "165") (name "unconnected-(IC2L-IO_L10P_T1_37-PadD8)") (class "Default")
      (node (ref "IC2") (pin "D8") (pinfunction "IO_L10P_T1_37_D8") (pintype "bidirectional"))
    )
    (net (code "166") (name "unconnected-(IC2L-IO_L11N_T1_SRCC_37-PadE7)") (class "Default")
      (node (ref "IC2") (pin "E7") (pinfunction "IO_L11N_T1_SRCC_37_E7") (pintype "bidirectional"))
    )
    (net (code "167") (name "unconnected-(IC2L-IO_L11P_T1_SRCC_37-PadE8)") (class "Default")
      (node (ref "IC2") (pin "E8") (pinfunction "IO_L11P_T1_SRCC_37_E8") (pintype "bidirectional"))
    )
    (net (code "168") (name "unconnected-(IC2L-IO_L12N_T1_MRCC_37-PadC6)") (class "Default")
      (node (ref "IC2") (pin "C6") (pinfunction "IO_L12N_T1_MRCC_37_C6") (pintype "bidirectional"))
    )
    (net (code "169") (name "unconnected-(IC2L-IO_L12P_T1_MRCC_37-PadC7)") (class "Default")
      (node (ref "IC2") (pin "C7") (pinfunction "IO_L12P_T1_MRCC_37_C7") (pintype "bidirectional"))
    )
    (net (code "170") (name "unconnected-(IC2L-IO_L13N_T2_MRCC_37-PadD5)") (class "Default")
      (node (ref "IC2") (pin "D5") (pinfunction "IO_L13N_T2_MRCC_37_D5") (pintype "bidirectional"))
    )
    (net (code "171") (name "unconnected-(IC2L-IO_L13P_T2_MRCC_37-PadD6)") (class "Default")
      (node (ref "IC2") (pin "D6") (pinfunction "IO_L13P_T2_MRCC_37_D6") (pintype "bidirectional"))
    )
    (net (code "172") (name "unconnected-(IC2L-IO_L14N_T2_SRCC_37-PadE5)") (class "Default")
      (node (ref "IC2") (pin "E5") (pinfunction "IO_L14N_T2_SRCC_37_E5") (pintype "bidirectional"))
    )
    (net (code "173") (name "unconnected-(IC2L-IO_L14P_T2_SRCC_37-PadE6)") (class "Default")
      (node (ref "IC2") (pin "E6") (pinfunction "IO_L14P_T2_SRCC_37_E6") (pintype "bidirectional"))
    )
    (net (code "174") (name "unconnected-(IC2L-IO_L15N_T2_DQS_37-PadA4)") (class "Default")
      (node (ref "IC2") (pin "A4") (pinfunction "IO_L15N_T2_DQS_37_A4") (pintype "bidirectional"))
    )
    (net (code "175") (name "unconnected-(IC2L-IO_L15P_T2_DQS_37-PadB4)") (class "Default")
      (node (ref "IC2") (pin "B4") (pinfunction "IO_L15P_T2_DQS_37_B4") (pintype "bidirectional"))
    )
    (net (code "176") (name "unconnected-(IC2L-IO_L16N_T2_37-PadA5)") (class "Default")
      (node (ref "IC2") (pin "A5") (pinfunction "IO_L16N_T2_37_A5") (pintype "bidirectional"))
    )
    (net (code "177") (name "unconnected-(IC2L-IO_L16P_T2_37-PadB5)") (class "Default")
      (node (ref "IC2") (pin "B5") (pinfunction "IO_L16P_T2_37_B5") (pintype "bidirectional"))
    )
    (net (code "178") (name "unconnected-(IC2L-IO_L17N_T2_37-PadC4)") (class "Default")
      (node (ref "IC2") (pin "C4") (pinfunction "IO_L17N_T2_37_C4") (pintype "bidirectional"))
    )
    (net (code "179") (name "unconnected-(IC2L-IO_L17P_T2_37-PadD4)") (class "Default")
      (node (ref "IC2") (pin "D4") (pinfunction "IO_L17P_T2_37_D4") (pintype "bidirectional"))
    )
    (net (code "180") (name "unconnected-(IC2L-IO_L18N_T2_37-PadF4)") (class "Default")
      (node (ref "IC2") (pin "F4") (pinfunction "IO_L18N_T2_37_F4") (pintype "bidirectional"))
    )
    (net (code "181") (name "unconnected-(IC2L-IO_L18P_T2_37-PadF5)") (class "Default")
      (node (ref "IC2") (pin "F5") (pinfunction "IO_L18P_T2_37_F5") (pintype "bidirectional"))
    )
    (net (code "182") (name "unconnected-(IC2L-IO_L19N_T3_VREF_37-PadC3)") (class "Default")
      (node (ref "IC2") (pin "C3") (pinfunction "IO_L19N_T3_VREF_37_C3") (pintype "bidirectional"))
    )
    (net (code "183") (name "unconnected-(IC2L-IO_L19P_T3_37-PadD3)") (class "Default")
      (node (ref "IC2") (pin "D3") (pinfunction "IO_L19P_T3_37_D3") (pintype "bidirectional"))
    )
    (net (code "184") (name "unconnected-(IC2L-IO_L20N_T3_37-PadA2)") (class "Default")
      (node (ref "IC2") (pin "A2") (pinfunction "IO_L20N_T3_37_A2") (pintype "bidirectional"))
    )
    (net (code "185") (name "unconnected-(IC2L-IO_L20P_T3_37-PadA3)") (class "Default")
      (node (ref "IC2") (pin "A3") (pinfunction "IO_L20P_T3_37_A3") (pintype "bidirectional"))
    )
    (net (code "186") (name "unconnected-(IC2L-IO_L21N_T3_DQS_37-PadB2)") (class "Default")
      (node (ref "IC2") (pin "B2") (pinfunction "IO_L21N_T3_DQS_37_B2") (pintype "bidirectional"))
    )
    (net (code "187") (name "unconnected-(IC2L-IO_L21P_T3_DQS_37-PadC2)") (class "Default")
      (node (ref "IC2") (pin "C2") (pinfunction "IO_L21P_T3_DQS_37_C2") (pintype "bidirectional"))
    )
    (net (code "188") (name "unconnected-(IC2L-IO_L22N_T3_37-PadB1)") (class "Default")
      (node (ref "IC2") (pin "B1") (pinfunction "IO_L22N_T3_37_B1") (pintype "bidirectional"))
    )
    (net (code "189") (name "unconnected-(IC2L-IO_L22P_T3_37-PadC1)") (class "Default")
      (node (ref "IC2") (pin "C1") (pinfunction "IO_L22P_T3_37_C1") (pintype "bidirectional"))
    )
    (net (code "190") (name "unconnected-(IC2L-IO_L23N_T3_37-PadD1)") (class "Default")
      (node (ref "IC2") (pin "D1") (pinfunction "IO_L23N_T3_37_D1") (pintype "bidirectional"))
    )
    (net (code "191") (name "unconnected-(IC2L-IO_L23P_T3_37-PadE1)") (class "Default")
      (node (ref "IC2") (pin "E1") (pinfunction "IO_L23P_T3_37_E1") (pintype "bidirectional"))
    )
    (net (code "192") (name "unconnected-(IC2L-IO_L24N_T3_37-PadE2)") (class "Default")
      (node (ref "IC2") (pin "E2") (pinfunction "IO_L24N_T3_37_E2") (pintype "bidirectional"))
    )
    (net (code "193") (name "unconnected-(IC2L-IO_L24P_T3_37-PadE3)") (class "Default")
      (node (ref "IC2") (pin "E3") (pinfunction "IO_L24P_T3_37_E3") (pintype "bidirectional"))
    )
    (net (code "194") (name "unconnected-(J1-Pada4)") (class "Default")
      (node (ref "J1") (pin "a4") (pinfunction "a4_a4") (pintype "bidirectional"))
    )
    (net (code "195") (name "unconnected-(J1-Pada10)") (class "Default")
      (node (ref "J1") (pin "a10") (pinfunction "a10_a10") (pintype "bidirectional"))
    )
    (net (code "196") (name "unconnected-(J1-Padb4)") (class "Default")
      (node (ref "J1") (pin "b4") (pinfunction "b4_b4") (pintype "bidirectional"))
    )
    (net (code "197") (name "unconnected-(J1-Padb7)") (class "Default")
      (node (ref "J1") (pin "b7") (pinfunction "b7_b7") (pintype "bidirectional"))
    )
    (net (code "198") (name "unconnected-(J1-Padb8)") (class "Default")
      (node (ref "J1") (pin "b8") (pinfunction "b8_b8") (pintype "bidirectional"))
    )
    (net (code "199") (name "unconnected-(J1-Padb9)") (class "Default")
      (node (ref "J1") (pin "b9") (pinfunction "b9_b9") (pintype "bidirectional"))
    )
    (net (code "200") (name "unconnected-(J1-Padb10)") (class "Default")
      (node (ref "J1") (pin "b10") (pinfunction "b10_b10") (pintype "bidirectional"))
    )
    (net (code "201") (name "unconnected-(J1-PadbG4)") (class "Default")
      (node (ref "J1") (pin "bG4") (pinfunction "bG4_bG4") (pintype "power_in"))
    )
    (net (code "202") (name "unconnected-(J1-Padc4)") (class "Default")
      (node (ref "J1") (pin "c4") (pinfunction "c4_c4") (pintype "bidirectional"))
    )
    (net (code "203") (name "unconnected-(J1-Padd4)") (class "Default")
      (node (ref "J1") (pin "d4") (pinfunction "d4_d4") (pintype "bidirectional"))
    )
    (net (code "204") (name "unconnected-(J1-Padd5)") (class "Default")
      (node (ref "J1") (pin "d5") (pinfunction "d5_d5") (pintype "bidirectional"))
    )
    (net (code "205") (name "unconnected-(J1-Padd6)") (class "Default")
      (node (ref "J1") (pin "d6") (pinfunction "d6_d6") (pintype "bidirectional"))
    )
    (net (code "206") (name "unconnected-(J1-Padd7)") (class "Default")
      (node (ref "J1") (pin "d7") (pinfunction "d7_d7") (pintype "bidirectional"))
    )
    (net (code "207") (name "unconnected-(J1-Padd8)") (class "Default")
      (node (ref "J1") (pin "d8") (pinfunction "d8_d8") (pintype "bidirectional"))
    )
    (net (code "208") (name "unconnected-(J1-Padd9)") (class "Default")
      (node (ref "J1") (pin "d9") (pinfunction "d9_d9") (pintype "bidirectional"))
    )
    (net (code "209") (name "unconnected-(J1-Padd10)") (class "Default")
      (node (ref "J1") (pin "d10") (pinfunction "d10_d10") (pintype "bidirectional"))
    )
    (net (code "210") (name "unconnected-(J1-Pade3)") (class "Default")
      (node (ref "J1") (pin "e3") (pinfunction "e3_e3") (pintype "bidirectional"))
    )
    (net (code "211") (name "unconnected-(J1-Pade4)") (class "Default")
      (node (ref "J1") (pin "e4") (pinfunction "e4_e4") (pintype "bidirectional"))
    )
    (net (code "212") (name "unconnected-(J1-Padf3)") (class "Default")
      (node (ref "J1") (pin "f3") (pinfunction "f3_f3") (pintype "bidirectional"))
    )
    (net (code "213") (name "unconnected-(J1-Padf4)") (class "Default")
      (node (ref "J1") (pin "f4") (pinfunction "f4_f4") (pintype "bidirectional"))
    )
    (net (code "214") (name "unconnected-(J2-Pada3)") (class "Default")
      (node (ref "J2") (pin "a3") (pinfunction "a3_a3") (pintype "bidirectional"))
    )
    (net (code "215") (name "unconnected-(J2-Pada4)") (class "Default")
      (node (ref "J2") (pin "a4") (pinfunction "a4_a4") (pintype "bidirectional"))
    )
    (net (code "216") (name "unconnected-(J2-Pada6)") (class "Default")
      (node (ref "J2") (pin "a6") (pinfunction "a6_a6") (pintype "bidirectional"))
    )
    (net (code "217") (name "unconnected-(J2-Pada7)") (class "Default")
      (node (ref "J2") (pin "a7") (pinfunction "a7_a7") (pintype "bidirectional"))
    )
    (net (code "218") (name "unconnected-(J2-Pada8)") (class "Default")
      (node (ref "J2") (pin "a8") (pinfunction "a8_a8") (pintype "bidirectional"))
    )
    (net (code "219") (name "unconnected-(J2-Pada10)") (class "Default")
      (node (ref "J2") (pin "a10") (pinfunction "a10_a10") (pintype "bidirectional"))
    )
    (net (code "220") (name "unconnected-(J2-Padb1)") (class "Default")
      (node (ref "J2") (pin "b1") (pinfunction "b1_b1") (pintype "bidirectional"))
    )
    (net (code "221") (name "unconnected-(J2-Padb2)") (class "Default")
      (node (ref "J2") (pin "b2") (pinfunction "b2_b2") (pintype "bidirectional"))
    )
    (net (code "222") (name "unconnected-(J2-Padb3)") (class "Default")
      (node (ref "J2") (pin "b3") (pinfunction "b3_b3") (pintype "bidirectional"))
    )
    (net (code "223") (name "unconnected-(J2-Padb4)") (class "Default")
      (node (ref "J2") (pin "b4") (pinfunction "b4_b4") (pintype "bidirectional"))
    )
    (net (code "224") (name "unconnected-(J2-Padb6)") (class "Default")
      (node (ref "J2") (pin "b6") (pinfunction "b6_b6") (pintype "bidirectional"))
    )
    (net (code "225") (name "unconnected-(J2-Padb7)") (class "Default")
      (node (ref "J2") (pin "b7") (pinfunction "b7_b7") (pintype "bidirectional"))
    )
    (net (code "226") (name "unconnected-(J2-Padb8)") (class "Default")
      (node (ref "J2") (pin "b8") (pinfunction "b8_b8") (pintype "bidirectional"))
    )
    (net (code "227") (name "unconnected-(J2-Padb10)") (class "Default")
      (node (ref "J2") (pin "b10") (pinfunction "b10_b10") (pintype "bidirectional"))
    )
    (net (code "228") (name "unconnected-(J2-Padd1)") (class "Default")
      (node (ref "J2") (pin "d1") (pinfunction "d1_d1") (pintype "bidirectional"))
    )
    (net (code "229") (name "unconnected-(J2-Padd2)") (class "Default")
      (node (ref "J2") (pin "d2") (pinfunction "d2_d2") (pintype "bidirectional"))
    )
    (net (code "230") (name "unconnected-(J2-Padf1)") (class "Default")
      (node (ref "J2") (pin "f1") (pinfunction "f1_f1") (pintype "bidirectional"))
    )
    (net (code "231") (name "unconnected-(J2-Padf2)") (class "Default")
      (node (ref "J2") (pin "f2") (pinfunction "f2_f2") (pintype "bidirectional"))
    )
  )
)
